# power.net
KiCad netlist of a schematic drawn in EAGLE
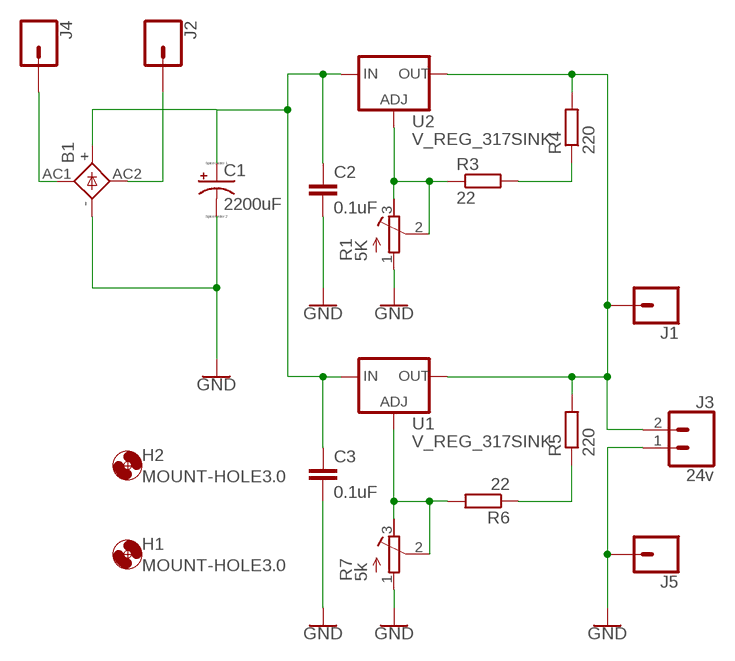
[diagram p0: schematic, sheet 1]

(export (version "E")
  (design (tool "Eeschema 10.0.6"))
  (components
    (comp (ref "B1")
      (value "GBPC1")
      (footprint "eagle-import:GBPC1")
      (libsource (lib "eagle-import") (part "GBPC1"))
    )
    (comp (ref "C1")
      (value "2200uF")
      (footprint "eagle-import:E7,5-16")
      (libsource (lib "eagle-import") (part "CPOL-USE7.5-16"))
    )
    (comp (ref "C2")
      (value "0.1uF")
      (footprint "eagle-import:C025-024X044")
      (libsource (lib "eagle-import") (part "C-EU025-024X044"))
    )
    (comp (ref "C3")
      (value "0.1uF")
      (footprint "eagle-import:C025-024X044")
      (libsource (lib "eagle-import") (part "C-EU025-024X044"))
    )
    (comp (ref "H1")
      (value "MOUNT-HOLE3.0")
      (footprint "eagle-import:3,0")
      (libsource (lib "eagle-import") (part "MOUNT-HOLE3.0"))
    )
    (comp (ref "H2")
      (value "MOUNT-HOLE3.0")
      (footprint "eagle-import:3,0")
      (libsource (lib "eagle-import") (part "MOUNT-HOLE3.0"))
    )
    (comp (ref "J1")
      (value "CONN_01PTH_2MM")
      (footprint "eagle-import:1X01_2MM")
      (libsource (lib "eagle-import") (part "CONN_01PTH_2MM"))
    )
    (comp (ref "J2")
      (value "CONN_01PTH_2MM")
      (footprint "eagle-import:1X01_2MM")
      (libsource (lib "eagle-import") (part "CONN_01PTH_2MM"))
    )
    (comp (ref "J3")
      (value "24v")
      (footprint "eagle-import:SCREWTERMINAL-5MM-2")
      (libsource (lib "eagle-import") (part "CONN_025MM"))
    )
    (comp (ref "J4")
      (value "CONN_01PTH_2MM")
      (footprint "eagle-import:1X01_2MM")
      (libsource (lib "eagle-import") (part "CONN_01PTH_2MM"))
    )
    (comp (ref "J5")
      (value "CONN_01PTH_2MM")
      (footprint "eagle-import:1X01_2MM")
      (libsource (lib "eagle-import") (part "CONN_01PTH_2MM"))
    )
    (comp (ref "R1")
      (value "5K")
      (footprint "eagle-import:RTRIM64W")
      (libsource (lib "eagle-import") (part "R-TRIMM64W"))
    )
    (comp (ref "R3")
      (value "22")
      (footprint "eagle-import:0207_10")
      (libsource (lib "eagle-import") (part "R-EU_0207/10"))
    )
    (comp (ref "R4")
      (value "220")
      (footprint "eagle-import:0207_10")
      (libsource (lib "eagle-import") (part "R-EU_0207/10"))
    )
    (comp (ref "R5")
      (value "220")
      (footprint "eagle-import:0207_10")
      (libsource (lib "eagle-import") (part "R-EU_0207/10"))
    )
    (comp (ref "R6")
      (value "22")
      (footprint "eagle-import:0207_10")
      (libsource (lib "eagle-import") (part "R-EU_0207/10"))
    )
    (comp (ref "R7")
      (value "5k")
      (footprint "eagle-import:RTRIM64W")
      (libsource (lib "eagle-import") (part "R-TRIMM64W"))
    )
    (comp (ref "U1")
      (value "V_REG_317SINK")
      (footprint "eagle-import:TO220-ADJ")
      (libsource (lib "eagle-import") (part "V_REG_317SINK"))
    )
    (comp (ref "U2")
      (value "V_REG_317SINK")
      (footprint "eagle-import:TO220-ADJ")
      (libsource (lib "eagle-import") (part "V_REG_317SINK"))
    )
  )
  (nets
    (net (code "1") (name "GND") (class "Default")
      (node (ref "B1") (pin "-") (pinfunction "-_-") (pintype "passive"))
      (node (ref "C1") (pin "-") (pinfunction "-_-") (pintype "passive"))
      (node (ref "C2") (pin "2") (pinfunction "2_2") (pintype "passive"))
      (node (ref "C3") (pin "2") (pinfunction "2_2") (pintype "passive"))
      (node (ref "J3") (pin "1") (pinfunction "1_1") (pintype "passive"))
      (node (ref "J5") (pin "1") (pinfunction "1_1") (pintype "passive"))
      (node (ref "R1") (pin "1") (pinfunction "A_1") (pintype "passive"))
      (node (ref "R7") (pin "1") (pinfunction "A_1") (pintype "passive"))
    )
    (net (code "2") (name "Net-(B1-Pad+)") (class "Default")
      (node (ref "B1") (pin "+") (pinfunction "+_+") (pintype "passive"))
      (node (ref "C1") (pin "+") (pinfunction "+_+") (pintype "passive"))
      (node (ref "C2") (pin "1") (pinfunction "1_1") (pintype "passive"))
      (node (ref "C3") (pin "1") (pinfunction "1_1") (pintype "passive"))
      (node (ref "U1") (pin "IN") (pinfunction "IN_IN") (pintype "input"))
      (node (ref "U2") (pin "IN") (pinfunction "IN_IN") (pintype "input"))
    )
    (net (code "3") (name "Net-(B1-PadAC1)") (class "Default")
      (node (ref "B1") (pin "AC1") (pinfunction "AC1_AC1") (pintype "passive"))
      (node (ref "J4") (pin "1") (pinfunction "1_1") (pintype "passive"))
    )
    (net (code "4") (name "Net-(B1-PadAC2)") (class "Default")
      (node (ref "B1") (pin "AC2") (pinfunction "AC2_AC2") (pintype "passive"))
      (node (ref "J2") (pin "1") (pinfunction "1_1") (pintype "passive"))
    )
    (net (code "5") (name "Net-(J1-Pad1)") (class "Default")
      (node (ref "J1") (pin "1") (pinfunction "1_1") (pintype "passive"))
      (node (ref "J3") (pin "2") (pinfunction "2_2") (pintype "passive"))
      (node (ref "R4") (pin "2") (pinfunction "2_2") (pintype "passive"))
      (node (ref "R5") (pin "2") (pinfunction "2_2") (pintype "passive"))
      (node (ref "U1") (pin "OUT") (pinfunction "OUT_OUT") (pintype "output"))
      (node (ref "U2") (pin "OUT") (pinfunction "OUT_OUT") (pintype "output"))
    )
    (net (code "6") (name "Net-(R1-E)") (class "Default")
      (node (ref "R1") (pin "2") (pinfunction "S_2") (pintype "passive"))
      (node (ref "R1") (pin "3") (pinfunction "E_3") (pintype "passive"))
      (node (ref "R3") (pin "1") (pinfunction "1_1") (pintype "passive"))
      (node (ref "U2") (pin "ADJ") (pinfunction "ADJ_ADJ") (pintype "input"))
    )
    (net (code "7") (name "Net-(R3-Pad2)") (class "Default")
      (node (ref "R3") (pin "2") (pinfunction "2_2") (pintype "passive"))
      (node (ref "R4") (pin "1") (pinfunction "1_1") (pintype "passive"))
    )
    (net (code "8") (name "Net-(R5-Pad1)") (class "Default")
      (node (ref "R5") (pin "1") (pinfunction "1_1") (pintype "passive"))
      (node (ref "R6") (pin "1") (pinfunction "1_1") (pintype "passive"))
    )
    (net (code "9") (name "Net-(R7-E)") (class "Default")
      (node (ref "R6") (pin "2") (pinfunction "2_2") (pintype "passive"))
      (node (ref "R7") (pin "2") (pinfunction "S_2") (pintype "passive"))
      (node (ref "R7") (pin "3") (pinfunction "E_3") (pintype "passive"))
      (node (ref "U1") (pin "ADJ") (pinfunction "ADJ_ADJ") (pintype "input"))
    )
  )
)
